# TMP116.net
KiCad netlist of a schematic drawn in Altium Designer
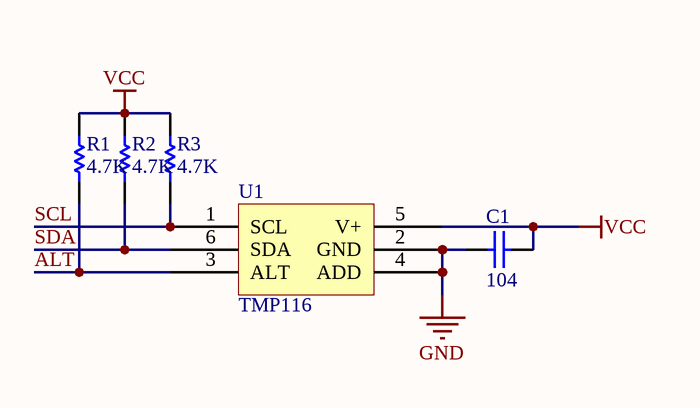
[diagram p0: TMP116.SchDoc]

(export (version "E")
  (design (tool "Eeschema 10.0.6"))
  (components
    (comp (ref "C1")
      (value "104")
      (footprint "0402")
      (description "Capacitor (Semiconductor SIM Model)")
      (fields (field (name "Comment") "Cap Semi") (field (name "PUBLISHER") "Altium Limited"))
      (libsource (lib "Miscellaneous Devices") (part "Cap Semi"))
    )
    (comp (ref "R1")
      (value "4.7K")
      (footprint "0402")
      (description "Resistor")
      (fields (field (name "Comment") "Res1") (field (name "PUBLISHER") "Altium Limited"))
      (libsource (lib "Miscellaneous Devices") (part "Res1"))
    )
    (comp (ref "R2")
      (value "4.7K")
      (footprint "0402")
      (description "Resistor")
      (fields (field (name "Comment") "Res1") (field (name "PUBLISHER") "Altium Limited"))
      (libsource (lib "Miscellaneous Devices") (part "Res1"))
    )
    (comp (ref "R3")
      (value "4.7K")
      (footprint "0402")
      (description "Resistor")
      (fields (field (name "Comment") "Res1") (field (name "PUBLISHER") "Altium Limited"))
      (libsource (lib "Miscellaneous Devices") (part "Res1"))
    )
    (comp (ref "U1")
      (value "TMP116")
      (footprint "WSON")
      (fields (field (name "Comment") "Sensor"))
      (libsource (lib "Tank") (part "TMP116"))
    )
  )
  (nets
    (net (code "1") (name "/ALT") (class "Default")
      (node (ref "R1") (pin "2") (pinfunction "2_2") (pintype "passive"))
      (node (ref "U1") (pin "3") (pinfunction "ALT_3") (pintype "passive"))
    )
    (net (code "2") (name "/SCL") (class "Default")
      (node (ref "R3") (pin "2") (pinfunction "2_2") (pintype "passive"))
      (node (ref "U1") (pin "1") (pinfunction "SCL_1") (pintype "passive"))
    )
    (net (code "3") (name "/SDA") (class "Default")
      (node (ref "R2") (pin "2") (pinfunction "2_2") (pintype "passive"))
      (node (ref "U1") (pin "6") (pinfunction "SDA_6") (pintype "passive"))
    )
    (net (code "4") (name "GND") (class "Default")
      (node (ref "C1") (pin "1") (pinfunction "1_1") (pintype "passive"))
      (node (ref "U1") (pin "2") (pinfunction "GND_2") (pintype "passive"))
      (node (ref "U1") (pin "4") (pinfunction "ADD_4") (pintype "passive"))
    )
    (net (code "5") (name "VCC") (class "Default")
      (node (ref "C1") (pin "2") (pinfunction "2_2") (pintype "passive"))
      (node (ref "R1") (pin "1") (pinfunction "1_1") (pintype "passive"))
      (node (ref "R2") (pin "1") (pinfunction "1_1") (pintype "passive"))
      (node (ref "R3") (pin "1") (pinfunction "1_1") (pintype "passive"))
      (node (ref "U1") (pin "5") (pinfunction "V+_5") (pintype "passive"))
    )
  )
)
